# remote_tester.net
KiCad netlist of a schematic drawn in EAGLE
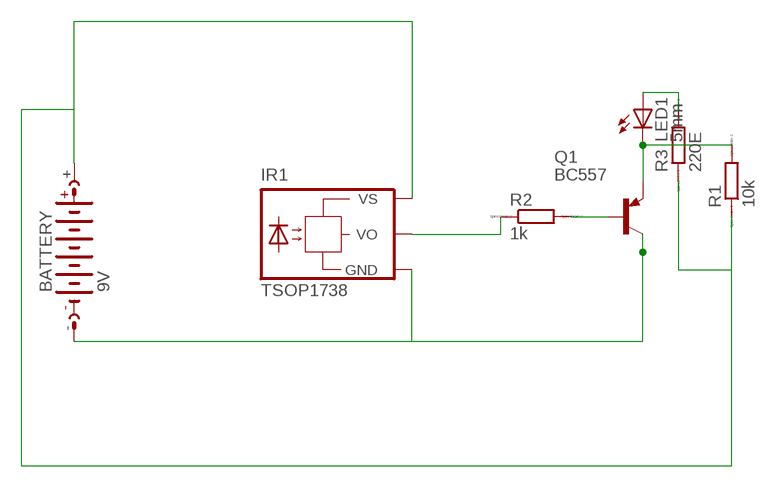
[diagram p0: schematic, sheet 1]

(export (version "E")
  (design (tool "Eeschema 10.0.6"))
  (components
    (comp (ref "BATTERY")
      (value "9V")
      (footprint "eagle-import:AB9V")
      (libsource (lib "eagle-import") (part "AB9V"))
    )
    (comp (ref "IR1")
      (value "TSOP1738")
      (footprint "eagle-import:TSOP17_TB1")
      (libsource (lib "eagle-import") (part "TSOP17TB130"))
    )
    (comp (ref "LED1")
      (value "5mm")
      (footprint "eagle-import:LED5MM")
      (libsource (lib "eagle-import") (part "LED5MM"))
    )
    (comp (ref "Q1")
      (value "BC557")
      (footprint "eagle-import:TO92")
      (libsource (lib "eagle-import") (part "BC557"))
    )
    (comp (ref "R1")
      (value "10k")
      (footprint "eagle-import:0204_7")
      (libsource (lib "eagle-import") (part "R0204/7"))
    )
    (comp (ref "R2")
      (value "1k")
      (footprint "eagle-import:0204_7")
      (libsource (lib "eagle-import") (part "R0204/7"))
    )
    (comp (ref "R3")
      (value "220E")
      (footprint "eagle-import:0204_7")
      (libsource (lib "eagle-import") (part "R0204/7"))
    )
  )
  (nets
    (net (code "1") (name "Net-(BATTERY-Pad+)") (class "Default")
      (node (ref "BATTERY") (pin "+") (pinfunction "+_+") (pintype "passive"))
      (node (ref "IR1") (pin "VS") (pinfunction "VS_VS") (pintype "power_in"))
      (node (ref "R1") (pin "1") (pinfunction "1_1") (pintype "passive"))
      (node (ref "R3") (pin "1") (pinfunction "1_1") (pintype "passive"))
    )
    (net (code "2") (name "Net-(IR1-PadVO)") (class "Default")
      (node (ref "IR1") (pin "VO") (pinfunction "VO_VO") (pintype "open_collector"))
      (node (ref "R2") (pin "1") (pinfunction "1_1") (pintype "passive"))
    )
    (net (code "3") (name "Net-(LED1-C)") (class "Default")
      (node (ref "LED1") (pin "K") (pinfunction "C_K") (pintype "passive"))
      (node (ref "Q1") (pin "1") (pinfunction "E_1") (pintype "passive"))
      (node (ref "R1") (pin "2") (pinfunction "2_2") (pintype "passive"))
    )
    (net (code "4") (name "Net-(LED1-PadA)") (class "Default")
      (node (ref "LED1") (pin "A") (pinfunction "A_A") (pintype "passive"))
      (node (ref "R3") (pin "2") (pinfunction "2_2") (pintype "passive"))
    )
    (net (code "5") (name "Net-(Q1-B)") (class "Default")
      (node (ref "Q1") (pin "2") (pinfunction "B_2") (pintype "passive"))
      (node (ref "R2") (pin "2") (pinfunction "2_2") (pintype "passive"))
    )
    (net (code "6") (name "Net-(Q1-C)") (class "Default")
      (node (ref "BATTERY") (pin "-") (pinfunction "-_-") (pintype "passive"))
      (node (ref "IR1") (pin "GND") (pinfunction "GND_GND") (pintype "power_in"))
      (node (ref "Q1") (pin "3") (pinfunction "C_3") (pintype "passive"))
    )
  )
)
